# Motor_MCU.net
KiCad netlist of a schematic drawn in Altium Designer
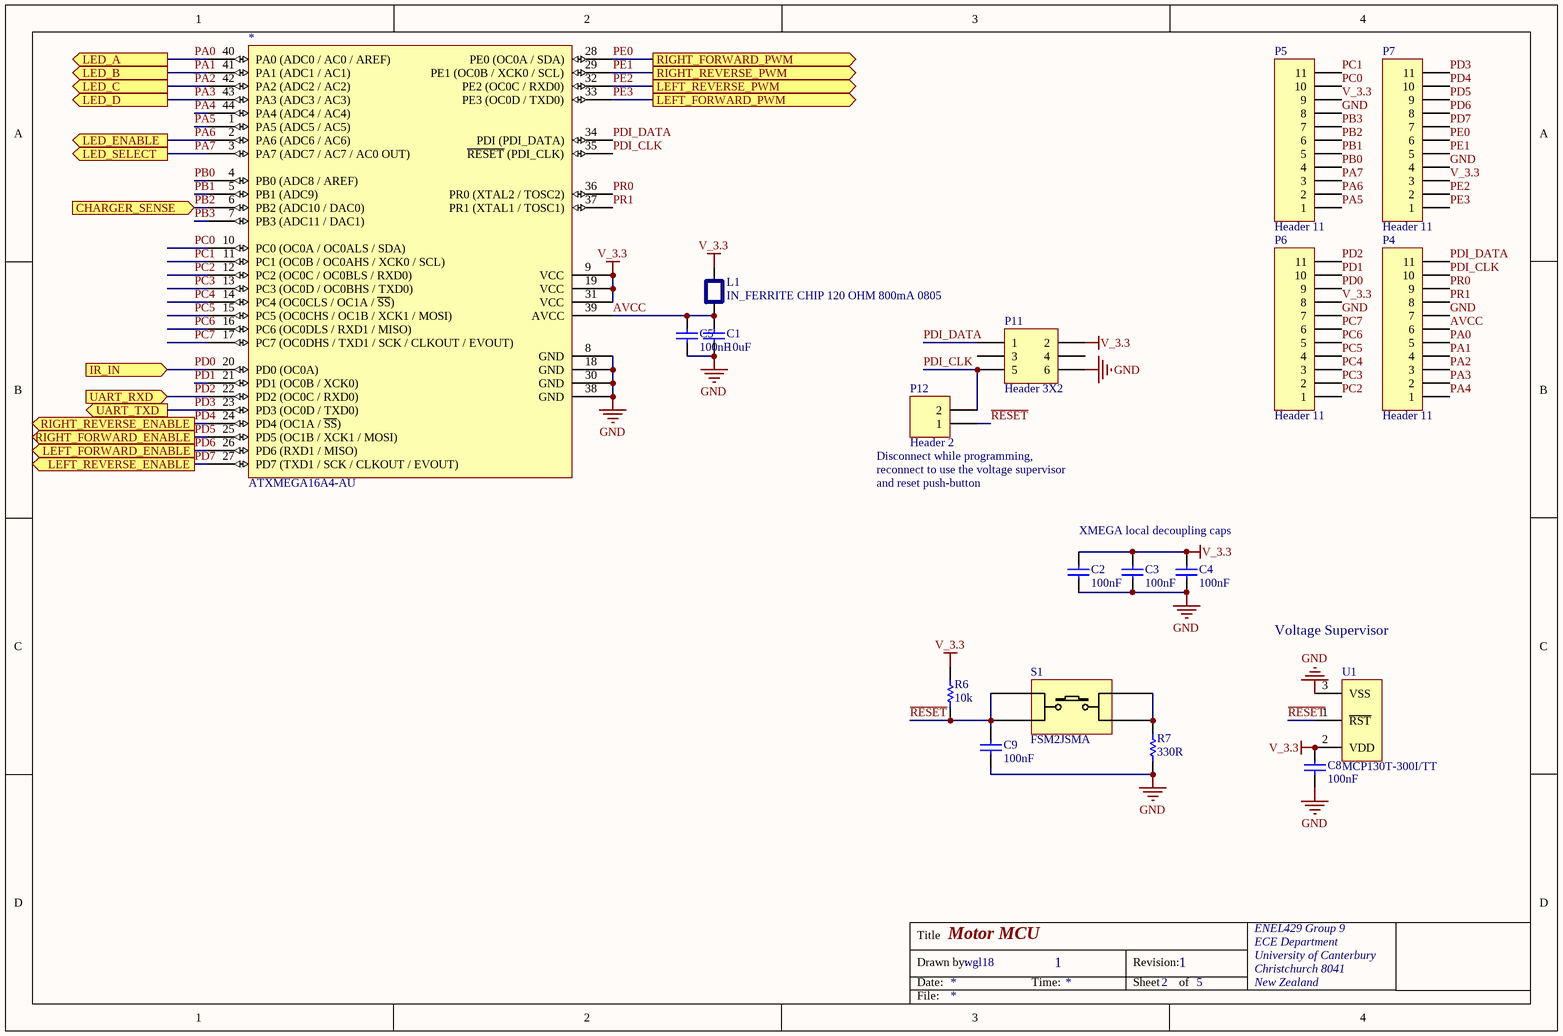
[diagram p0: Motor_MCU.SchDoc]

(export (version "E")
  (design (tool "Eeschema 10.0.6"))
  (components
    (comp (ref "*")
      (value "ATXMEGA16A4-AU")
      (footprint "TQFP80P1200X1200X120-44N")
      (fields (field (name "MANUFACTURER") "ATMEL"))
      (libsource (lib "Wacky_1") (part "ATXMEGA16A4-AU"))
    )
    (comp (ref "C1")
      (value "10uF")
      (footprint "0805")
      (description "CAP 10uF 10% 10V X5R 0805")
      (fields (field (name "PART NUMBER") "CP_10uF 0805") (field (name "MANUFACTURER") "Murata"))
      (libsource (lib "ENEL429_4") (part "CP_10uF 0805"))
    )
    (comp (ref "C2")
      (value "100nF")
      (footprint "0603")
      (description "CAP CER .10UF 50V X5R 0603")
      (fields (field (name "PART NUMBER") "CP_100nF 0603") (field (name "MANUFACTURER") "Taiyo Yuden"))
      (libsource (lib "ENEL429_4") (part "CP_100nF 0603"))
    )
    (comp (ref "C3")
      (value "100nF")
      (footprint "0603")
      (description "CAP CER .10UF 50V X5R 0603")
      (fields (field (name "PART NUMBER") "CP_100nF 0603") (field (name "MANUFACTURER") "Taiyo Yuden"))
      (libsource (lib "ENEL429_4") (part "CP_100nF 0603"))
    )
    (comp (ref "C4")
      (value "100nF")
      (footprint "0603")
      (description "CAP CER .10UF 50V X5R 0603")
      (fields (field (name "PART NUMBER") "CP_100nF 0603") (field (name "MANUFACTURER") "Taiyo Yuden"))
      (libsource (lib "ENEL429_4") (part "CP_100nF 0603"))
    )
    (comp (ref "C5")
      (value "100nF")
      (footprint "0603")
      (description "CAP CER .10UF 50V X5R 0603")
      (fields (field (name "PART NUMBER") "CP_100nF 0603") (field (name "MANUFACTURER") "Taiyo Yuden"))
      (libsource (lib "ENEL429_4") (part "CP_100nF 0603"))
    )
    (comp (ref "C8")
      (value "100nF")
      (footprint "0603")
      (description "CAP CER .10UF 50V X5R 0603")
      (fields (field (name "PART NUMBER") "CP_100nF 0603") (field (name "MANUFACTURER") "Taiyo Yuden"))
      (libsource (lib "ENEL429_4") (part "CP_100nF 0603"))
    )
    (comp (ref "C9")
      (value "100nF")
      (footprint "0603")
      (description "CAP CER .10UF 50V X5R 0603")
      (fields (field (name "PART NUMBER") "CP_100nF 0603") (field (name "MANUFACTURER") "Taiyo Yuden"))
      (libsource (lib "ENEL429_4") (part "CP_100nF 0603"))
    )
    (comp (ref "L1")
      (value "IN_FERRITE CHIP 120 OHM 800mA 0805")
      (footprint "0805")
      (description "FERRITE CHIP 120 OHM 800mA 0805")
      (fields (field (name "MANUFACTURER") "TDK"))
      (libsource (lib "ENEL429_4") (part "IN_FERRITE CHIP 120 OHM 800mA 0805"))
    )
    (comp (ref "P4")
      (value "Header 11")
      (footprint "HDR1X11")
      (description "Header, 11-Pin")
      (fields (field (name "PUBLISHER") "Altium Limited"))
      (libsource (lib "Miscellaneous Connectors") (part "Header 11"))
    )
    (comp (ref "P5")
      (value "Header 11")
      (footprint "HDR1X11")
      (description "Header, 11-Pin")
      (fields (field (name "PUBLISHER") "Altium Limited"))
      (libsource (lib "Miscellaneous Connectors") (part "Header 11"))
    )
    (comp (ref "P6")
      (value "Header 11")
      (footprint "HDR1X11")
      (description "Header, 11-Pin")
      (fields (field (name "PUBLISHER") "Altium Limited"))
      (libsource (lib "Miscellaneous Connectors") (part "Header 11"))
    )
    (comp (ref "P7")
      (value "Header 11")
      (footprint "HDR1X11")
      (description "Header, 11-Pin")
      (fields (field (name "PUBLISHER") "Altium Limited"))
      (libsource (lib "Miscellaneous Connectors") (part "Header 11"))
    )
    (comp (ref "P11")
      (value "Header 3X2")
      (footprint "HDR2X3")
      (description "Header, 3-Pin, Dual row")
      (fields (field (name "PUBLISHER") "Altium Limited"))
      (libsource (lib "Miscellaneous Connectors") (part "Header 3X2"))
    )
    (comp (ref "P12")
      (value "Header 2")
      (footprint "HDR1X2")
      (description "Header, 2-Pin")
      (fields (field (name "PUBLISHER") "Altium Limited"))
      (libsource (lib "Miscellaneous Connectors") (part "Header 2"))
    )
    (comp (ref "R6")
      (value "10k")
      (footprint "0603")
      (description "RES 10.0K OHM 1/10W 1% 0603 SMD")
      (fields (field (name "PART NUMBER") "RS_10k 0603") (field (name "MANUFACTURER") "Yageo"))
      (libsource (lib "ENEL429_4") (part "RS_10k 0603"))
    )
    (comp (ref "R7")
      (value "330R")
      (footprint "0603")
      (description "RES 330 OHM 1/10W 1% 0603 SMD")
      (fields (field (name "PART NUMBER") "RS_330R 0603") (field (name "MANUFACTURER") "Yageo"))
      (libsource (lib "ENEL429_4") (part "RS_330R 0603"))
    )
    (comp (ref "S1")
      (value "FSM2JSMA")
      (footprint "FSM2JSMA")
      (description "DPST SMD Switch")
      (fields (field (name "MANUFACTURER") "Tyco Electronics") (field (name "PART NUMBER") "SW_FSM2JSMA"))
      (libsource (lib "ENEL429_4") (part "SW_FSM2JSMA"))
    )
    (comp (ref "U1")
      (value "MCP130T-300I/TT")
      (footprint "SOT-23-TT3_N")
      (fields (field (name "PUBLISHER") "Altium Limited"))
      (libsource (lib "Microchip Power Mgt CPU-System Supervisor") (part "MCP130T-300I/TT"))
    )
  )
  (nets
    (net (code "1") (name "/AVCC") (class "Default")
      (node (ref "*") (pin "39") (pinfunction "AVCC_39") (pintype "passive"))
      (node (ref "C1") (pin "1") (pinfunction "1_1") (pintype "passive"))
      (node (ref "C5") (pin "2") (pinfunction "2_2") (pintype "passive"))
      (node (ref "L1") (pin "2") (pinfunction "1_2") (pintype "power_in"))
      (node (ref "P4") (pin "6") (pinfunction "6_6") (pintype "passive"))
    )
    (net (code "2") (name "/PA0") (class "Default")
      (node (ref "*") (pin "40") (pinfunction "PA0_(ADC0_/_AC0_/_AREF)_40") (pintype "bidirectional"))
      (node (ref "P4") (pin "5") (pinfunction "5_5") (pintype "passive"))
    )
    (net (code "3") (name "/PA1") (class "Default")
      (node (ref "*") (pin "41") (pinfunction "PA1_(ADC1_/_AC1)_41") (pintype "bidirectional"))
      (node (ref "P4") (pin "4") (pinfunction "4_4") (pintype "passive"))
    )
    (net (code "4") (name "/PA2") (class "Default")
      (node (ref "*") (pin "42") (pinfunction "PA2_(ADC2_/_AC2)_42") (pintype "bidirectional"))
      (node (ref "P4") (pin "3") (pinfunction "3_3") (pintype "passive"))
    )
    (net (code "5") (name "/PA3") (class "Default")
      (node (ref "*") (pin "43") (pinfunction "PA3_(ADC3_/_AC3)_43") (pintype "bidirectional"))
      (node (ref "P4") (pin "2") (pinfunction "2_2") (pintype "passive"))
    )
    (net (code "6") (name "/PA4") (class "Default")
      (node (ref "*") (pin "44") (pinfunction "PA4_(ADC4_/_AC4)_44") (pintype "bidirectional"))
      (node (ref "P4") (pin "1") (pinfunction "1_1") (pintype "passive"))
    )
    (net (code "7") (name "/PA5") (class "Default")
      (node (ref "*") (pin "1") (pinfunction "PA5_(ADC5_/_AC5)_1") (pintype "bidirectional"))
      (node (ref "P5") (pin "1") (pinfunction "1_1") (pintype "passive"))
    )
    (net (code "8") (name "/PA6") (class "Default")
      (node (ref "*") (pin "2") (pinfunction "PA6_(ADC6_/_AC6)_2") (pintype "bidirectional"))
      (node (ref "P5") (pin "2") (pinfunction "2_2") (pintype "passive"))
    )
    (net (code "9") (name "/PA7") (class "Default")
      (node (ref "*") (pin "3") (pinfunction "PA7_(ADC7_/_AC7_/_AC0_OUT)_3") (pintype "bidirectional"))
      (node (ref "P5") (pin "3") (pinfunction "3_3") (pintype "passive"))
    )
    (net (code "10") (name "/PB0") (class "Default")
      (node (ref "*") (pin "4") (pinfunction "PB0_(ADC8_/_AREF)_4") (pintype "bidirectional"))
      (node (ref "P5") (pin "4") (pinfunction "4_4") (pintype "passive"))
    )
    (net (code "11") (name "/PB1") (class "Default")
      (node (ref "*") (pin "5") (pinfunction "PB1_(ADC9)_5") (pintype "bidirectional"))
      (node (ref "P5") (pin "5") (pinfunction "5_5") (pintype "passive"))
    )
    (net (code "12") (name "/PB2") (class "Default")
      (node (ref "*") (pin "6") (pinfunction "PB2_(ADC10_/_DAC0)_6") (pintype "bidirectional"))
      (node (ref "P5") (pin "6") (pinfunction "6_6") (pintype "passive"))
    )
    (net (code "13") (name "/PB3") (class "Default")
      (node (ref "*") (pin "7") (pinfunction "PB3_(ADC11_/_DAC1)_7") (pintype "bidirectional"))
      (node (ref "P5") (pin "7") (pinfunction "7_7") (pintype "passive"))
    )
    (net (code "14") (name "/PC0") (class "Default")
      (node (ref "*") (pin "10") (pinfunction "PC0_(OC0A_/_OC0ALS_/_SDA)_10") (pintype "bidirectional"))
      (node (ref "P5") (pin "10") (pinfunction "10_10") (pintype "passive"))
    )
    (net (code "15") (name "/PC1") (class "Default")
      (node (ref "*") (pin "11") (pinfunction "PC1_(OC0B_/_OC0AHS_/_XCK0_/_SCL)_11") (pintype "bidirectional"))
      (node (ref "P5") (pin "11") (pinfunction "11_11") (pintype "passive"))
    )
    (net (code "16") (name "/PC2") (class "Default")
      (node (ref "*") (pin "12") (pinfunction "PC2_(OC0C_/_OC0BLS_/_RXD0)_12") (pintype "bidirectional"))
      (node (ref "P6") (pin "1") (pinfunction "1_1") (pintype "passive"))
    )
    (net (code "17") (name "/PC3") (class "Default")
      (node (ref "*") (pin "13") (pinfunction "PC3_(OC0D_/_OC0BHS_/_TXD0)_13") (pintype "bidirectional"))
      (node (ref "P6") (pin "2") (pinfunction "2_2") (pintype "passive"))
    )
    (net (code "18") (name "/PC4") (class "Default")
      (node (ref "*") (pin "14") (pinfunction "PC4_(OC0CLS_/_OC1A_/_~{SS})_14") (pintype "bidirectional"))
      (node (ref "P6") (pin "3") (pinfunction "3_3") (pintype "passive"))
    )
    (net (code "19") (name "/PC5") (class "Default")
      (node (ref "*") (pin "15") (pinfunction "PC5_(OC0CHS_/_OC1B_/_XCK1_/_MOSI)_15") (pintype "bidirectional"))
      (node (ref "P6") (pin "4") (pinfunction "4_4") (pintype "passive"))
    )
    (net (code "20") (name "/PC6") (class "Default")
      (node (ref "*") (pin "16") (pinfunction "PC6_(OC0DLS_/_RXD1_/_MISO)_16") (pintype "bidirectional"))
      (node (ref "P6") (pin "5") (pinfunction "5_5") (pintype "passive"))
    )
    (net (code "21") (name "/PC7") (class "Default")
      (node (ref "*") (pin "17") (pinfunction "PC7_(OC0DHS_/_TXD1_/_SCK_/_CLKOUT_/_EVOUT)_17") (pintype "bidirectional"))
      (node (ref "P6") (pin "6") (pinfunction "6_6") (pintype "passive"))
    )
    (net (code "22") (name "/PD0") (class "Default")
      (node (ref "*") (pin "20") (pinfunction "PD0_(OC0A)_20") (pintype "bidirectional"))
      (node (ref "P6") (pin "9") (pinfunction "9_9") (pintype "passive"))
    )
    (net (code "23") (name "/PD1") (class "Default")
      (node (ref "*") (pin "21") (pinfunction "PD1_(OC0B_/_XCK0)_21") (pintype "bidirectional"))
      (node (ref "P6") (pin "10") (pinfunction "10_10") (pintype "passive"))
    )
    (net (code "24") (name "/PD2") (class "Default")
      (node (ref "*") (pin "22") (pinfunction "PD2_(OC0C_/_RXD0)_22") (pintype "bidirectional"))
      (node (ref "P6") (pin "11") (pinfunction "11_11") (pintype "passive"))
    )
    (net (code "25") (name "/PD3") (class "Default")
      (node (ref "*") (pin "23") (pinfunction "PD3_(OC0D_/_TXD0)_23") (pintype "bidirectional"))
      (node (ref "P7") (pin "11") (pinfunction "11_11") (pintype "passive"))
    )
    (net (code "26") (name "/PD4") (class "Default")
      (node (ref "*") (pin "24") (pinfunction "PD4_(OC1A_/_~{SS})_24") (pintype "bidirectional"))
      (node (ref "P7") (pin "10") (pinfunction "10_10") (pintype "passive"))
    )
    (net (code "27") (name "/PD5") (class "Default")
      (node (ref "*") (pin "25") (pinfunction "PD5_(OC1B_/_XCK1_/_MOSI)_25") (pintype "bidirectional"))
      (node (ref "P7") (pin "9") (pinfunction "9_9") (pintype "passive"))
    )
    (net (code "28") (name "/PD6") (class "Default")
      (node (ref "*") (pin "26") (pinfunction "PD6_(RXD1_/_MISO)_26") (pintype "bidirectional"))
      (node (ref "P7") (pin "8") (pinfunction "8_8") (pintype "passive"))
    )
    (net (code "29") (name "/PD7") (class "Default")
      (node (ref "*") (pin "27") (pinfunction "PD7_(TXD1_/_SCK_/_CLKOUT_/_EVOUT)_27") (pintype "bidirectional"))
      (node (ref "P7") (pin "7") (pinfunction "7_7") (pintype "passive"))
    )
    (net (code "30") (name "/PDI_CLK") (class "Default")
      (node (ref "*") (pin "35") (pinfunction "~{RESET}_(PDI_CLK)_35") (pintype "bidirectional"))
      (node (ref "P11") (pin "5") (pinfunction "5_5") (pintype "passive"))
      (node (ref "P12") (pin "2") (pinfunction "2_2") (pintype "passive"))
      (node (ref "P4") (pin "10") (pinfunction "10_10") (pintype "passive"))
    )
    (net (code "31") (name "/PDI_DATA") (class "Default")
      (node (ref "*") (pin "34") (pinfunction "PDI_(PDI_DATA)_34") (pintype "bidirectional"))
      (node (ref "P11") (pin "1") (pinfunction "1_1") (pintype "passive"))
      (node (ref "P4") (pin "11") (pinfunction "11_11") (pintype "passive"))
    )
    (net (code "32") (name "/PE0") (class "Default")
      (node (ref "*") (pin "28") (pinfunction "PE0_(OC0A_/_SDA)_28") (pintype "bidirectional"))
      (node (ref "P7") (pin "6") (pinfunction "6_6") (pintype "passive"))
    )
    (net (code "33") (name "/PE1") (class "Default")
      (node (ref "*") (pin "29") (pinfunction "PE1_(OC0B_/_XCK0_/_SCL)_29") (pintype "bidirectional"))
      (node (ref "P7") (pin "5") (pinfunction "5_5") (pintype "passive"))
    )
    (net (code "34") (name "/PE2") (class "Default")
      (node (ref "*") (pin "32") (pinfunction "PE2_(OC0C_/_RXD0)_32") (pintype "bidirectional"))
      (node (ref "P7") (pin "2") (pinfunction "2_2") (pintype "passive"))
    )
    (net (code "35") (name "/PE3") (class "Default")
      (node (ref "*") (pin "33") (pinfunction "PE3_(OC0D_/_TXD0)_33") (pintype "bidirectional"))
      (node (ref "P7") (pin "1") (pinfunction "1_1") (pintype "passive"))
    )
    (net (code "36") (name "/PR0") (class "Default")
      (node (ref "*") (pin "36") (pinfunction "PR0_(XTAL2_/_TOSC2)_36") (pintype "bidirectional"))
      (node (ref "P4") (pin "9") (pinfunction "9_9") (pintype "passive"))
    )
    (net (code "37") (name "/PR1") (class "Default")
      (node (ref "*") (pin "37") (pinfunction "PR1_(XTAL1_/_TOSC1)_37") (pintype "bidirectional"))
      (node (ref "P4") (pin "8") (pinfunction "8_8") (pintype "passive"))
    )
    (net (code "38") (name "/~{RESET}") (class "Default")
      (node (ref "C9") (pin "1") (pinfunction "1_1") (pintype "passive"))
      (node (ref "P12") (pin "1") (pinfunction "1_1") (pintype "passive"))
      (node (ref "R6") (pin "1") (pinfunction "1_1") (pintype "passive"))
      (node (ref "S1") (pin "1") (pinfunction "1_1") (pintype "passive"))
      (node (ref "S1") (pin "2") (pinfunction "2_2") (pintype "passive"))
      (node (ref "U1") (pin "1") (pinfunction "~{RST}_1") (pintype "open_collector"))
    )
    (net (code "39") (name "GND") (class "Default")
      (node (ref "*") (pin "18") (pinfunction "GND_18") (pintype "passive"))
      (node (ref "*") (pin "30") (pinfunction "GND_30") (pintype "passive"))
      (node (ref "*") (pin "38") (pinfunction "GND_38") (pintype "passive"))
      (node (ref "*") (pin "8") (pinfunction "GND_8") (pintype "passive"))
      (node (ref "C1") (pin "2") (pinfunction "2_2") (pintype "passive"))
      (node (ref "C2") (pin "1") (pinfunction "1_1") (pintype "passive"))
      (node (ref "C3") (pin "1") (pinfunction "1_1") (pintype "passive"))
      (node (ref "C4") (pin "1") (pinfunction "1_1") (pintype "passive"))
      (node (ref "C5") (pin "1") (pinfunction "1_1") (pintype "passive"))
      (node (ref "C8") (pin "2") (pinfunction "2_2") (pintype "passive"))
      (node (ref "C9") (pin "2") (pinfunction "2_2") (pintype "passive"))
      (node (ref "P11") (pin "6") (pinfunction "6_6") (pintype "passive"))
      (node (ref "P4") (pin "7") (pinfunction "7_7") (pintype "passive"))
      (node (ref "P5") (pin "8") (pinfunction "8_8") (pintype "passive"))
      (node (ref "P6") (pin "7") (pinfunction "7_7") (pintype "passive"))
      (node (ref "P7") (pin "4") (pinfunction "4_4") (pintype "passive"))
      (node (ref "R7") (pin "1") (pinfunction "1_1") (pintype "passive"))
      (node (ref "U1") (pin "3") (pinfunction "VSS_3") (pintype "power_in"))
    )
    (net (code "40") (name "Net-(R7-Pad2)") (class "Default")
      (node (ref "R7") (pin "2") (pinfunction "2_2") (pintype "passive"))
      (node (ref "S1") (pin "3") (pinfunction "3_3") (pintype "passive"))
      (node (ref "S1") (pin "4") (pinfunction "4_4") (pintype "passive"))
    )
    (net (code "41") (name "V_3.3") (class "Default")
      (node (ref "*") (pin "19") (pinfunction "VCC_19") (pintype "passive"))
      (node (ref "*") (pin "31") (pinfunction "VCC_31") (pintype "passive"))
      (node (ref "*") (pin "9") (pinfunction "VCC_9") (pintype "passive"))
      (node (ref "C2") (pin "2") (pinfunction "2_2") (pintype "passive"))
      (node (ref "C3") (pin "2") (pinfunction "2_2") (pintype "passive"))
      (node (ref "C4") (pin "2") (pinfunction "2_2") (pintype "passive"))
      (node (ref "C8") (pin "1") (pinfunction "1_1") (pintype "passive"))
      (node (ref "L1") (pin "1") (pinfunction "0_1") (pintype "power_in"))
      (node (ref "P11") (pin "2") (pinfunction "2_2") (pintype "passive"))
      (node (ref "P5") (pin "9") (pinfunction "9_9") (pintype "passive"))
      (node (ref "P6") (pin "8") (pinfunction "8_8") (pintype "passive"))
      (node (ref "P7") (pin "3") (pinfunction "3_3") (pintype "passive"))
      (node (ref "R6") (pin "2") (pinfunction "2_2") (pintype "passive"))
      (node (ref "U1") (pin "2") (pinfunction "VDD_2") (pintype "power_in"))
    )
    (net (code "42") (name "unconnected-(P11-Pad3)") (class "Default")
      (node (ref "P11") (pin "3") (pinfunction "3_3") (pintype "passive"))
    )
    (net (code "43") (name "unconnected-(P11-Pad4)") (class "Default")
      (node (ref "P11") (pin "4") (pinfunction "4_4") (pintype "passive"))
    )
  )
)
